# tinycurrent.net
KiCad netlist of a schematic drawn in EAGLE
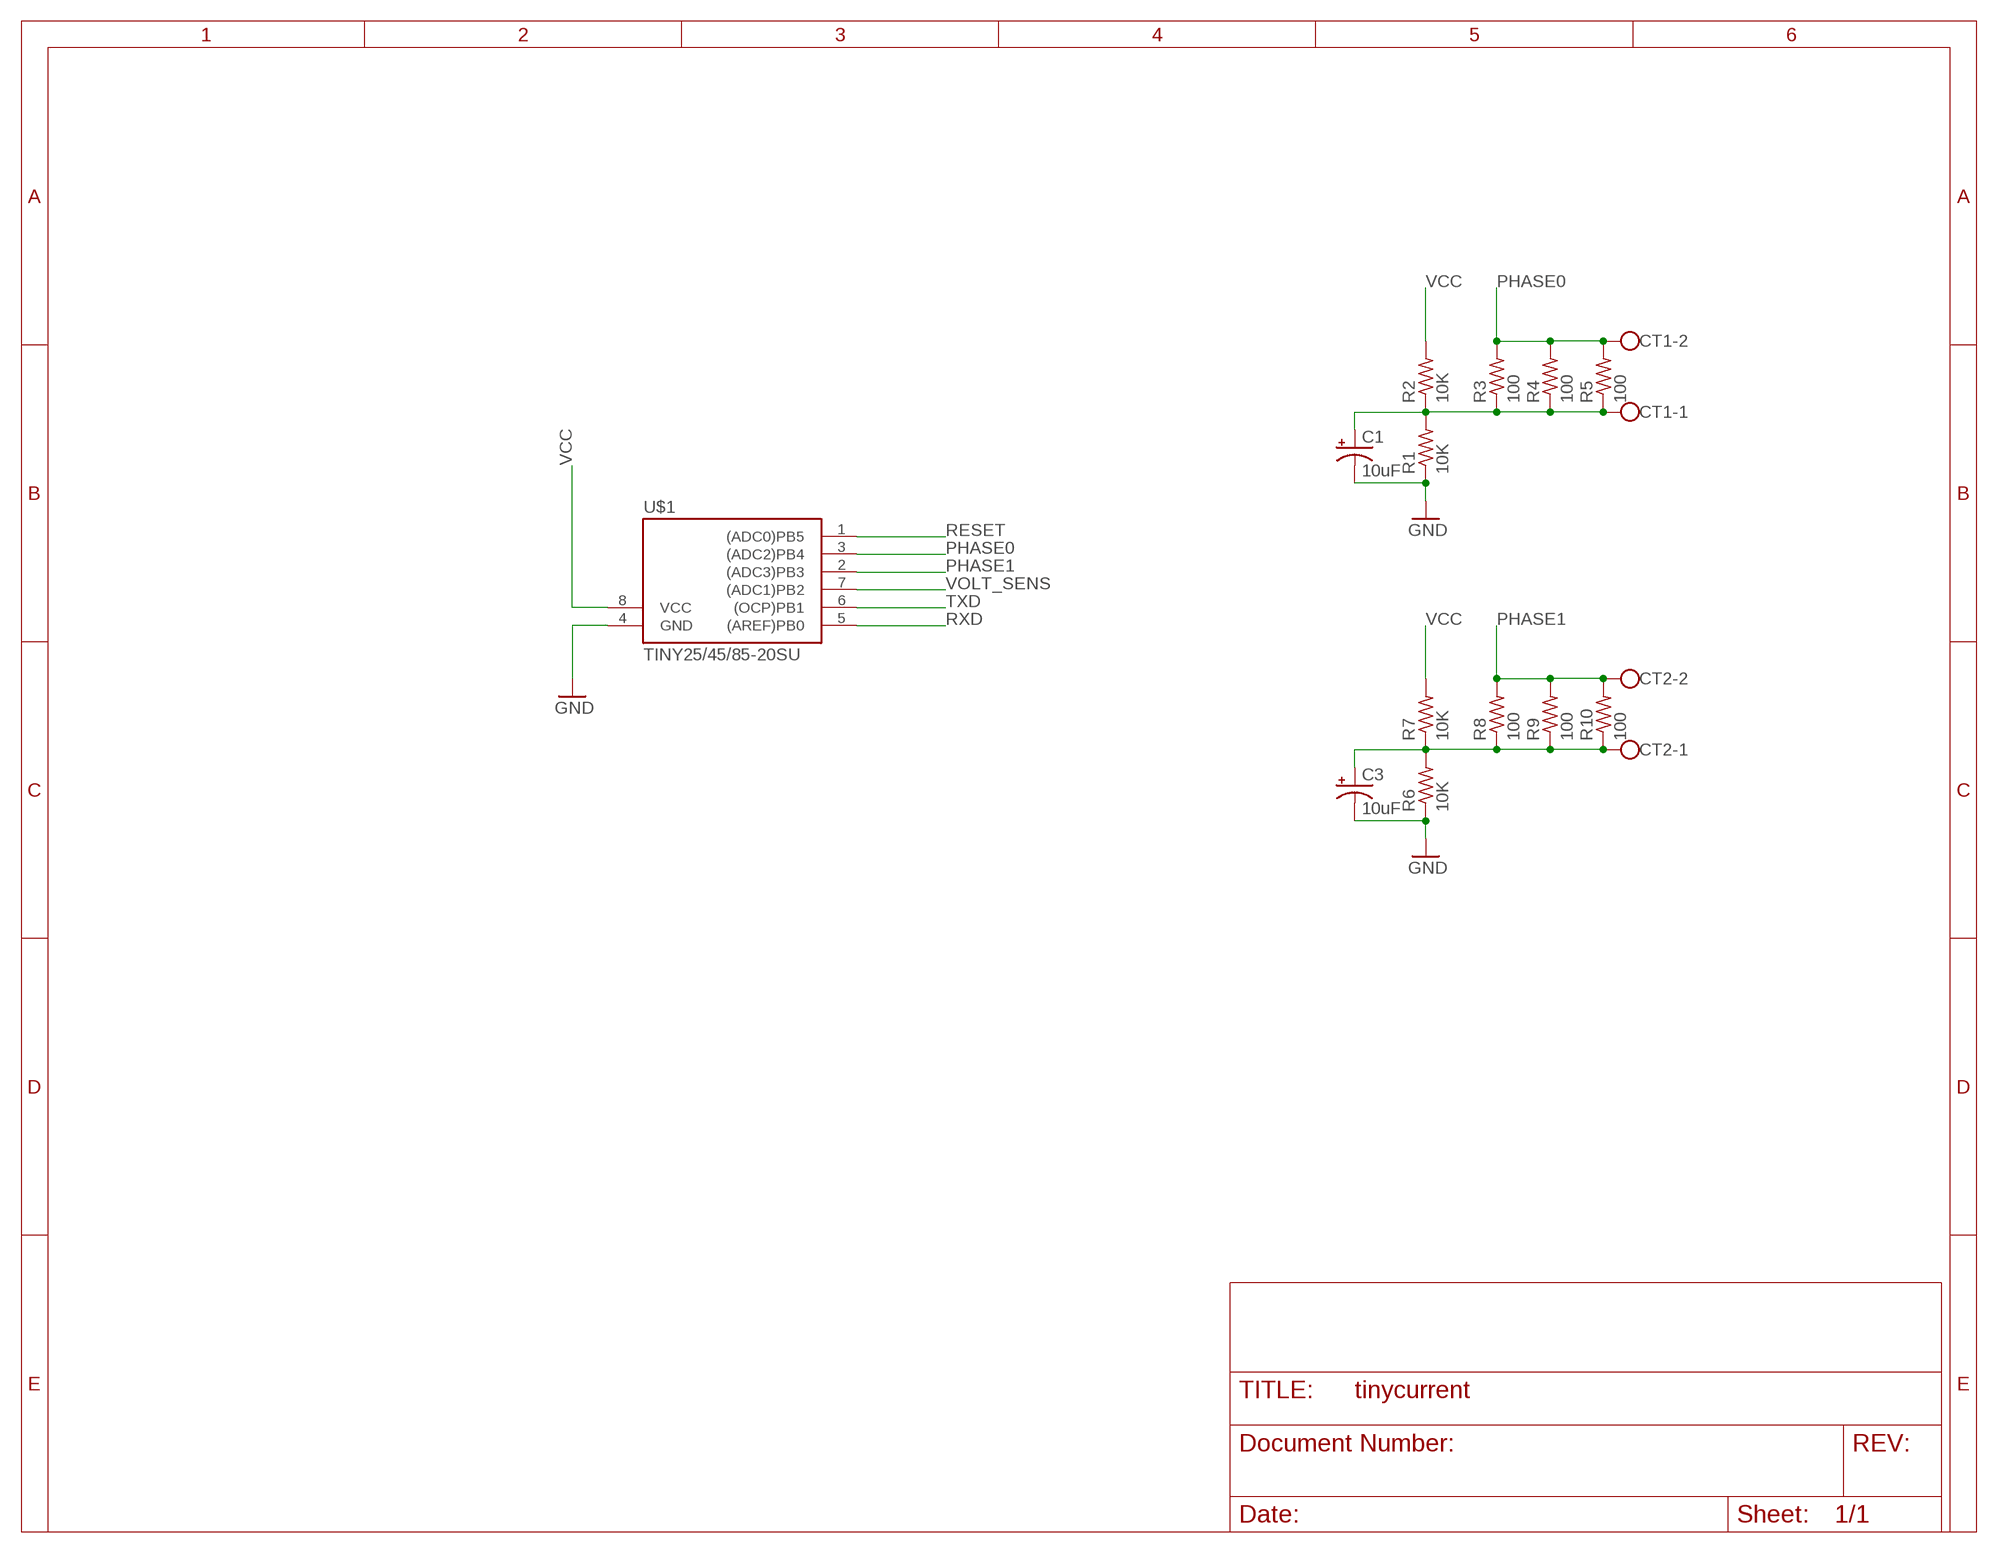
[diagram p0: schematic, sheet 1]

(export (version "E")
  (design (tool "Eeschema 10.0.6"))
  (components
    (comp (ref "C1")
      (value "10uF")
      (footprint "eagle-import:E5-8,5")
      (libsource (lib "eagle-import") (part "CPOL-USE5-8.5"))
    )
    (comp (ref "C3")
      (value "10uF")
      (footprint "eagle-import:E5-8,5")
      (libsource (lib "eagle-import") (part "CPOL-USE5-8.5"))
    )
    (comp (ref "CT1")
      (value "W237-102")
      (footprint "eagle-import:W237-102")
      (fields (field (name "MPN") "237-102"))
      (libsource (lib "eagle-import") (part "W237-102"))
    )
    (comp (ref "CT2")
      (value "W237-102")
      (footprint "eagle-import:W237-102")
      (fields (field (name "MPN") "237-102"))
      (libsource (lib "eagle-import") (part "W237-102"))
    )
    (comp (ref "R1")
      (value "10K")
      (footprint "eagle-import:0207_10")
      (libsource (lib "eagle-import") (part "R-US_0207/10"))
    )
    (comp (ref "R2")
      (value "10K")
      (footprint "eagle-import:0207_10")
      (libsource (lib "eagle-import") (part "R-US_0207/10"))
    )
    (comp (ref "R3")
      (value "100")
      (footprint "eagle-import:0207_10")
      (libsource (lib "eagle-import") (part "R-US_0207/10"))
    )
    (comp (ref "R4")
      (value "100")
      (footprint "eagle-import:0207_10")
      (libsource (lib "eagle-import") (part "R-US_0207/10"))
    )
    (comp (ref "R5")
      (value "100")
      (footprint "eagle-import:0207_10")
      (libsource (lib "eagle-import") (part "R-US_0207/10"))
    )
    (comp (ref "R6")
      (value "10K")
      (footprint "eagle-import:0207_10")
      (libsource (lib "eagle-import") (part "R-US_0207/10"))
    )
    (comp (ref "R7")
      (value "10K")
      (footprint "eagle-import:0207_10")
      (libsource (lib "eagle-import") (part "R-US_0207/10"))
    )
    (comp (ref "R8")
      (value "100")
      (footprint "eagle-import:0207_10")
      (libsource (lib "eagle-import") (part "R-US_0207/10"))
    )
    (comp (ref "R9")
      (value "100")
      (footprint "eagle-import:0207_10")
      (libsource (lib "eagle-import") (part "R-US_0207/10"))
    )
    (comp (ref "R10")
      (value "100")
      (footprint "eagle-import:0207_10")
      (libsource (lib "eagle-import") (part "R-US_0207/10"))
    )
    (comp (ref "U$1")
      (value "TINY25/45/85-20SU")
      (footprint "eagle-import:SOIC8")
      (libsource (lib "eagle-import") (part "TINY25/45/85-20SU"))
    )
  )
  (nets
    (net (code "1") (name "/PHASE0") (class "Default")
      (node (ref "CT1") (pin "2") (pinfunction "KL_2") (pintype "passive"))
      (node (ref "R3") (pin "2") (pinfunction "2_2") (pintype "passive"))
      (node (ref "R4") (pin "2") (pinfunction "2_2") (pintype "passive"))
      (node (ref "R5") (pin "2") (pinfunction "2_2") (pintype "passive"))
      (node (ref "U$1") (pin "3") (pinfunction "(ADC2)PB4_3") (pintype "bidirectional"))
    )
    (net (code "2") (name "/PHASE1") (class "Default")
      (node (ref "CT2") (pin "2") (pinfunction "KL_2") (pintype "passive"))
      (node (ref "R10") (pin "2") (pinfunction "2_2") (pintype "passive"))
      (node (ref "R8") (pin "2") (pinfunction "2_2") (pintype "passive"))
      (node (ref "R9") (pin "2") (pinfunction "2_2") (pintype "passive"))
      (node (ref "U$1") (pin "2") (pinfunction "(ADC3)PB3_2") (pintype "bidirectional"))
    )
    (net (code "3") (name "/RESET") (class "Default")
      (node (ref "U$1") (pin "1") (pinfunction "(ADC0)PB5_1") (pintype "bidirectional"))
    )
    (net (code "4") (name "/RXD") (class "Default")
      (node (ref "U$1") (pin "5") (pinfunction "(AREF)PB0_5") (pintype "bidirectional"))
    )
    (net (code "5") (name "/TXD") (class "Default")
      (node (ref "U$1") (pin "6") (pinfunction "(OCP)PB1_6") (pintype "bidirectional"))
    )
    (net (code "6") (name "/VCC") (class "Default")
      (node (ref "R2") (pin "2") (pinfunction "2_2") (pintype "passive"))
      (node (ref "R7") (pin "2") (pinfunction "2_2") (pintype "passive"))
      (node (ref "U$1") (pin "8") (pinfunction "VCC_8") (pintype "power_in"))
    )
    (net (code "7") (name "/VOLT_SENS") (class "Default")
      (node (ref "U$1") (pin "7") (pinfunction "(ADC1)PB2_7") (pintype "bidirectional"))
    )
    (net (code "8") (name "GND") (class "Default")
      (node (ref "C1") (pin "-") (pinfunction "-_-") (pintype "passive"))
      (node (ref "C3") (pin "-") (pinfunction "-_-") (pintype "passive"))
      (node (ref "R1") (pin "1") (pinfunction "1_1") (pintype "passive"))
      (node (ref "R6") (pin "1") (pinfunction "1_1") (pintype "passive"))
      (node (ref "U$1") (pin "4") (pinfunction "GND_4") (pintype "power_in"))
    )
    (net (code "9") (name "Net-(CT1A-KL)") (class "Default")
      (node (ref "C1") (pin "+") (pinfunction "+_+") (pintype "passive"))
      (node (ref "CT1") (pin "1") (pinfunction "KL_1") (pintype "passive"))
      (node (ref "R1") (pin "2") (pinfunction "2_2") (pintype "passive"))
      (node (ref "R2") (pin "1") (pinfunction "1_1") (pintype "passive"))
      (node (ref "R3") (pin "1") (pinfunction "1_1") (pintype "passive"))
      (node (ref "R4") (pin "1") (pinfunction "1_1") (pintype "passive"))
      (node (ref "R5") (pin "1") (pinfunction "1_1") (pintype "passive"))
    )
    (net (code "10") (name "Net-(CT2A-KL)") (class "Default")
      (node (ref "C3") (pin "+") (pinfunction "+_+") (pintype "passive"))
      (node (ref "CT2") (pin "1") (pinfunction "KL_1") (pintype "passive"))
      (node (ref "R10") (pin "1") (pinfunction "1_1") (pintype "passive"))
      (node (ref "R6") (pin "2") (pinfunction "2_2") (pintype "passive"))
      (node (ref "R7") (pin "1") (pinfunction "1_1") (pintype "passive"))
      (node (ref "R8") (pin "1") (pinfunction "1_1") (pintype "passive"))
      (node (ref "R9") (pin "1") (pinfunction "1_1") (pintype "passive"))
    )
  )
)
